# 7_P6_Gsensor.net
KiCad netlist of a schematic drawn in Altium Designer
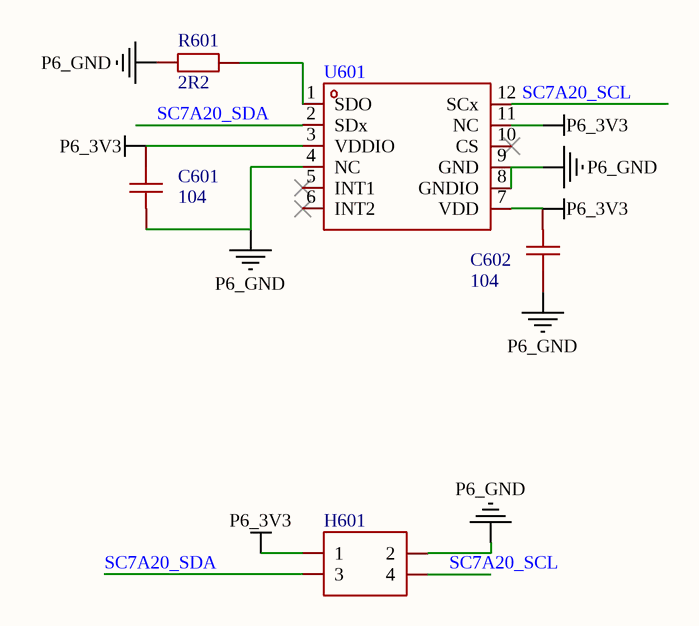
[diagram p0: 7_P6_Gsensor.schdoc]

(export (version "E")
  (design (tool "Eeschema 10.0.6"))
  (components
    (comp (ref "C601")
      (value "104")
      (footprint "C0603")
      (fields
        (field (name "MANUFACTURER") "HRE(芯声)")
        (field (name "MANUFACTURER PART") "CGA0603X7R104K500JT")
        (field (name "TOLERANCE") "±10%")
      )
      (libsource (lib "altium-import") (part "root_3_CGA0603X7R104K500JT_"))
    )
    (comp (ref "C602")
      (value "104")
      (footprint "C0603")
      (fields
        (field (name "MANUFACTURER") "HRE(芯声)")
        (field (name "MANUFACTURER PART") "CGA0603X7R104K500JT")
        (field (name "TOLERANCE") "±10%")
      )
      (libsource (lib "altium-import") (part "root_1_CGA0603X7R104K500JT_"))
    )
    (comp (ref "H601")
      (value "A2541HWV-2x2P")
      (footprint "Finger_2*2")
      (fields (field (name "MANUFACTURER") "CJT(长江连接器)"))
      (libsource (lib "altium-import") (part "root_0_A2541HWV-2x2P_"))
    )
    (comp (ref "R601")
      (value "2R2")
      (footprint "R0603")
      (libsource (lib "altium-import") (part "root_0_Res_0603_"))
    )
    (comp (ref "U601")
      (value "~")
      (footprint "LGA-12_L2.0-W2.0-P0.50-TL")
      (libsource (lib "altium-import") (part "root_0_SC7A20HTR_"))
    )
  )
  (nets
    (net (code "1") (name "/SC7A20_SCL") (class "Default")
      (node (ref "H601") (pin "4") (pinfunction "4_4") (pintype "passive"))
      (node (ref "U601") (pin "12") (pinfunction "SCx_12") (pintype "passive"))
    )
    (net (code "2") (name "/SC7A20_SDA") (class "Default")
      (node (ref "H601") (pin "3") (pinfunction "3_3") (pintype "passive"))
      (node (ref "U601") (pin "2") (pinfunction "SDx_2") (pintype "passive"))
    )
    (net (code "3") (name "Net-(U601-SDO)") (class "Default")
      (node (ref "R601") (pin "2") (pinfunction "2_2") (pintype "passive"))
      (node (ref "U601") (pin "1") (pinfunction "SDO_1") (pintype "passive"))
    )
    (net (code "4") (name "P6_3V3") (class "Default")
      (node (ref "C601") (pin "1") (pinfunction "1_1") (pintype "passive"))
      (node (ref "C602") (pin "2") (pinfunction "2_2") (pintype "passive"))
      (node (ref "H601") (pin "1") (pinfunction "1_1") (pintype "passive"))
      (node (ref "U601") (pin "11") (pinfunction "NC_11") (pintype "passive"))
      (node (ref "U601") (pin "3") (pinfunction "VDDIO_3") (pintype "passive"))
      (node (ref "U601") (pin "7") (pinfunction "VDD_7") (pintype "passive"))
    )
    (net (code "5") (name "P6_GND") (class "Default")
      (node (ref "C601") (pin "2") (pinfunction "2_2") (pintype "passive"))
      (node (ref "C602") (pin "1") (pinfunction "1_1") (pintype "passive"))
      (node (ref "H601") (pin "2") (pinfunction "2_2") (pintype "passive"))
      (node (ref "R601") (pin "1") (pinfunction "1_1") (pintype "passive"))
      (node (ref "U601") (pin "4") (pinfunction "NC_4") (pintype "passive"))
      (node (ref "U601") (pin "8") (pinfunction "GNDIO_8") (pintype "passive"))
      (node (ref "U601") (pin "9") (pinfunction "GND_9") (pintype "passive"))
    )
    (net (code "6") (name "unconnected-(U601-CS-Pad10)") (class "Default")
      (node (ref "U601") (pin "10") (pinfunction "CS_10") (pintype "passive+no_connect"))
    )
    (net (code "7") (name "unconnected-(U601-INT1-Pad5)") (class "Default")
      (node (ref "U601") (pin "5") (pinfunction "INT1_5") (pintype "passive+no_connect"))
    )
    (net (code "8") (name "unconnected-(U601-INT2-Pad6)") (class "Default")
      (node (ref "U601") (pin "6") (pinfunction "INT2_6") (pintype "passive+no_connect"))
    )
  )
)
